# SCH_-_Peripheral.net
KiCad netlist of a schematic drawn in Altium Designer
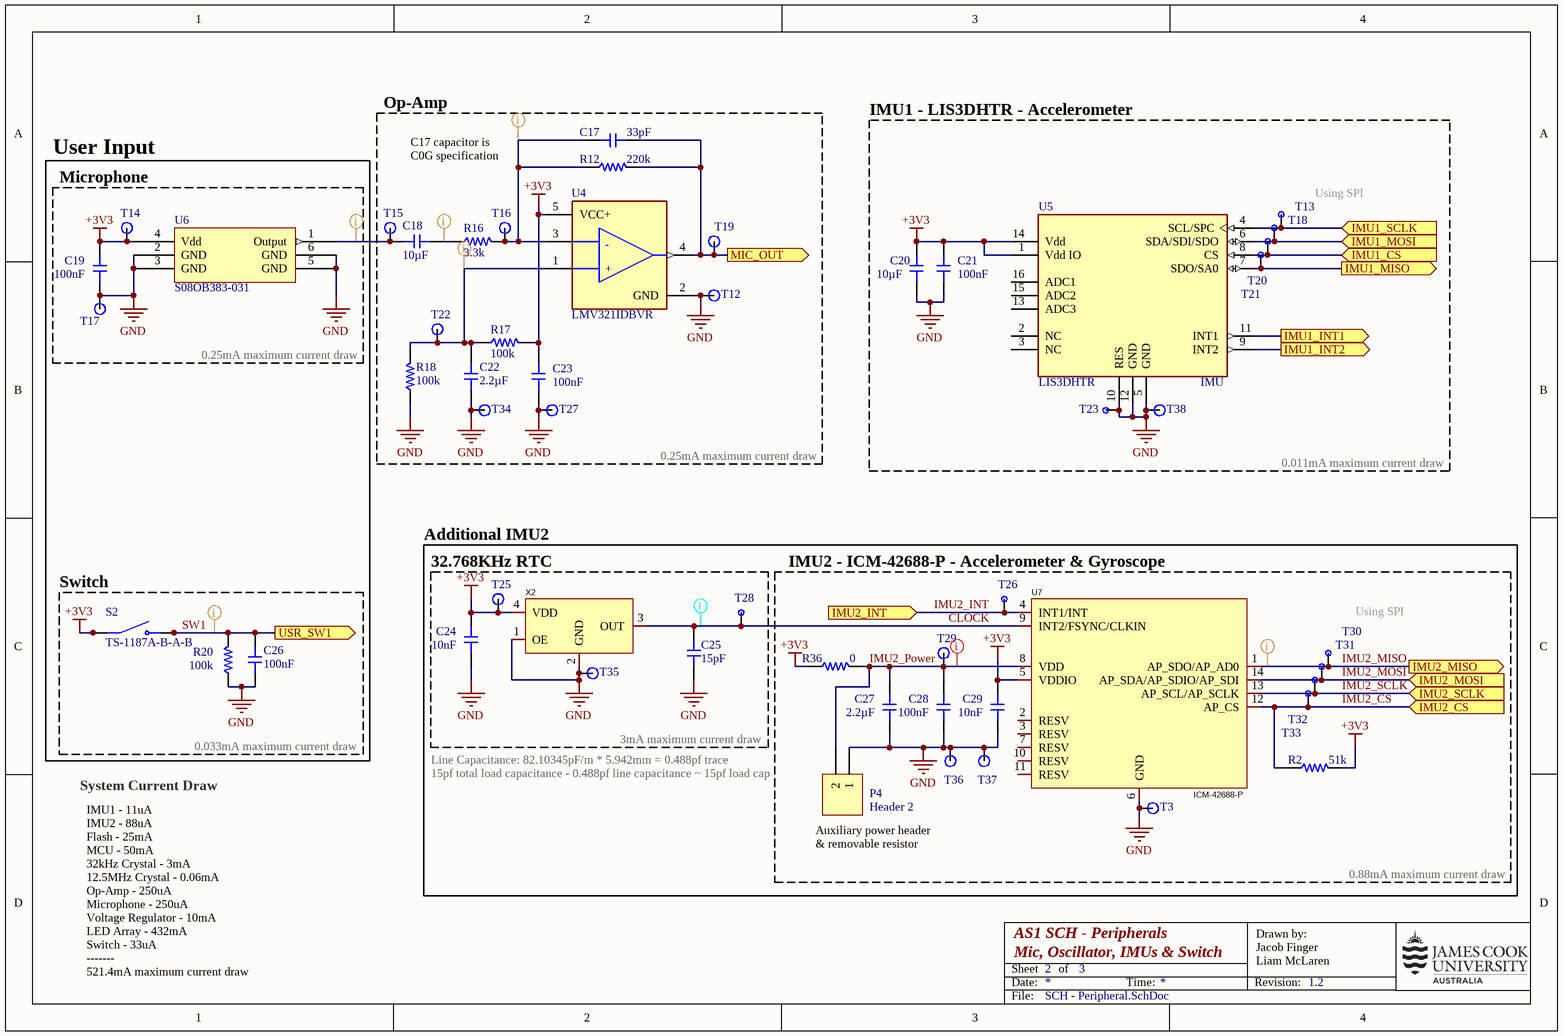
[diagram p0: SCH - Peripheral.SchDoc]

(export (version "E")
  (design (tool "Eeschema 10.0.6"))
  (components
    (comp (ref "C17")
      (value "33pF")
      (footprint "CAP-0402")
      (description "Capacitor, Ceramic (MLCC), 33pF, ±5%, 50V, C0G, ±5%, SMD 0402")
      (fields (field (name "TOLERANCE") "5%") (field (name "MANUFACTURER PART NUMBER") "0402CG330J500NT"))
      (libsource (lib "Finmac Systems") (part "GRM21BR61H106KE43L"))
    )
    (comp (ref "C18")
      (value "10µF")
      (footprint "CAP-0402")
      (description "Capacitor, Ceramic (MLCC), 10uF, ±20%, 6.3V, X5R, ±20%, SMD 0402")
      (fields
        (field (name "MANUFACTURER") "Samsung Electro-Mechanics")
        (field (name "JLCPCB PART NUMBER") "C15525")
      )
      (libsource (lib "Finmac Systems") (part "GRM21BR61H106KE43L"))
    )
    (comp (ref "C19")
      (value "100nF")
      (footprint "CAP-0402")
      (description "Capacitor, Ceramic (MLCC), 100nF, ±10%, 50V, X7R, ±10%, SMD 0402")
      (fields
        (field (name "MANUFACTURER PART NUMBER") "CL05B104KB54PNC")
        (field (name "MANUFACTURER") "Samsung Electro-Mechanics")
      )
      (libsource (lib "Finmac Systems") (part "GRM21BR61H106KE43L"))
    )
    (comp (ref "C20")
      (value "10µF")
      (footprint "CAP-0402")
      (description "Capacitor, Ceramic (MLCC), 10uF, ±20%, 6.3V, X5R, ±20%, SMD 0402")
      (fields
        (field (name "MANUFACTURER") "Samsung Electro-Mechanics")
        (field (name "JLCPCB PART NUMBER") "C15525")
      )
      (libsource (lib "Finmac Systems") (part "GRM21BR61H106KE43L"))
    )
    (comp (ref "C21")
      (value "100nF")
      (footprint "CAP-0402")
      (description "Capacitor, Ceramic (MLCC), 100nF, ±10%, 50V, X7R, ±10%, SMD 0402")
      (fields
        (field (name "MANUFACTURER PART NUMBER") "CL05B104KB54PNC")
        (field (name "MANUFACTURER") "Samsung Electro-Mechanics")
      )
      (libsource (lib "Finmac Systems") (part "GRM21BR61H106KE43L"))
    )
    (comp (ref "C22")
      (value "2.2µF")
      (footprint "CAP-0402")
      (description "Capacitor, Ceramic (MLCC), 2.2uF, ±20%, 6.3V, X5R, ±20%, SMD 0402")
      (fields
        (field (name "MANUFACTURER PART NUMBER") "CL05A225MQ5NSNC")
        (field (name "MANUFACTURER") "Samsung Electro-Mechanics")
      )
      (libsource (lib "Finmac Systems") (part "GRM21BR61H106KE43L"))
    )
    (comp (ref "C23")
      (value "100nF")
      (footprint "CAP-0402")
      (description "Capacitor, Ceramic (MLCC), 100nF, ±10%, 50V, X7R, ±10%, SMD 0402")
      (fields
        (field (name "MANUFACTURER PART NUMBER") "CL05B104KB54PNC")
        (field (name "MANUFACTURER") "Samsung Electro-Mechanics")
      )
      (libsource (lib "Finmac Systems") (part "GRM21BR61H106KE43L"))
    )
    (comp (ref "C24")
      (value "10nF")
      (footprint "CAP-0402")
      (description "Capacitor, Ceramic (MLCC), 10nF, ±10%, 50V, X7R, ±10%, SMD 0402")
      (fields (field (name "JLCPCB BASIC PART") "Yes") (field (name "JLCPCB PART NUMBER") "C15195"))
      (libsource (lib "Finmac Systems") (part "GRM21BR61H106KE43L"))
    )
    (comp (ref "C25")
      (value "15pF")
      (footprint "CAP-0402")
      (description "Capacitor, Ceramic (MLCC), 15pF, ±5%, 50V, C0G, ±5%, SMD 0402")
      (fields (field (name "TOLERANCE") "5%") (field (name "MANUFACTURER PART NUMBER") "0402CG150J500NT"))
      (libsource (lib "Finmac Systems") (part "GRM21BR61H106KE43L"))
    )
    (comp (ref "C26")
      (value "100nF")
      (footprint "CAP-0402")
      (description "Capacitor, Ceramic (MLCC), 100nF, ±10%, 16V, X7R, ±10%, SMD 0402")
      (fields
        (field (name "MANUFACTURER PART NUMBER") "CL05B104KO5NNNC")
        (field (name "MANUFACTURER") "Samsung Electro-Mechanics")
      )
      (libsource (lib "Finmac Systems") (part "GRM21BR61H106KE43L"))
    )
    (comp (ref "C27")
      (value "2.2µF")
      (footprint "CAP-0402")
      (description "Capacitor, Ceramic (MLCC), 2.2uF, ±20%, 6.3V, X5R, ±20%, SMD 0402")
      (fields
        (field (name "MANUFACTURER PART NUMBER") "CL05A225MQ5NSNC")
        (field (name "MANUFACTURER") "Samsung Electro-Mechanics")
      )
      (libsource (lib "Finmac Systems") (part "GRM21BR61H106KE43L"))
    )
    (comp (ref "C28")
      (value "100nF")
      (footprint "CAP-0402")
      (description "Capacitor, Ceramic (MLCC), 100nF, ±10%, 50V, X7R, ±10%, SMD 0402")
      (fields
        (field (name "MANUFACTURER PART NUMBER") "CL05B104KB54PNC")
        (field (name "MANUFACTURER") "Samsung Electro-Mechanics")
      )
      (libsource (lib "Finmac Systems") (part "GRM21BR61H106KE43L"))
    )
    (comp (ref "C29")
      (value "10nF")
      (footprint "CAP-0402")
      (description "Capacitor, Ceramic (MLCC), 10nF, ±10%, 50V, X7R, ±10%, SMD 0402")
      (fields (field (name "JLCPCB BASIC PART") "Yes") (field (name "JLCPCB PART NUMBER") "C15195"))
      (libsource (lib "Finmac Systems") (part "GRM21BR61H106KE43L"))
    )
    (comp (ref "P4")
      (value "Header 2")
      (footprint "HDR1X2")
      (description "Header, 2-Pin")
      (fields (field (name "PUBLISHER") "Altium Limited"))
      (libsource (lib "James Cook University") (part "Header 2H"))
    )
    (comp (ref "R2")
      (value "51k")
      (footprint "RES-0402")
      (description "Resistor, 51kΩ, ±1%, 62.5mW, 50V, ±100ppm/℃, -55℃~+155℃, SMD 0402")
      (fields
        (field (name "MANUFACTURER") "Uniroyal")
        (field (name "MANUFACTURER PART NUMBER") "0402WGF5102TCE")
      )
      (libsource (lib "Finmac Systems") (part "1206W4F7500T5E"))
    )
    (comp (ref "R12")
      (value "220k")
      (footprint "RES-0603")
      (description "Resistor, 220kΩ, ±1%, 100mW, 75V, ±100ppm/℃, -55℃~+155℃, SMD 0603")
      (fields (field (name "TOLERANCE") "1%") (field (name "MANUFACTURER PART NUMBER") "0603WAF2203T5E"))
      (libsource (lib "Finmac Systems") (part "1206W4F7500T5E"))
    )
    (comp (ref "R16")
      (value "3.3k")
      (footprint "RES-0402")
      (description "Resistor, 3.3kΩ, ±1%, 62.5mW, 50V, ±100ppm/℃, -55℃~+155℃, SMD 0402")
      (fields (field (name "JLCPCB PART NUMBER") "C25890") (field (name "MANUFACTURER") "Uniroyal"))
      (libsource (lib "Finmac Systems") (part "1206W4F7500T5E"))
    )
    (comp (ref "R17")
      (value "100k")
      (footprint "RES-0402")
      (description "Resistor, 100kΩ, ±1%, 62.5mW, 50V, ±100ppm/℃, -55℃~+155℃, SMD 0402")
      (fields (field (name "TOLERANCE") "1%") (field (name "MANUFACTURER") "Uniroyal"))
      (libsource (lib "Finmac Systems") (part "1206W4F7500T5E"))
    )
    (comp (ref "R18")
      (value "100k")
      (footprint "RES-0402")
      (description "Resistor, 100kΩ, ±1%, 62.5mW, 50V, ±100ppm/℃, -55℃~+155℃, SMD 0402")
      (fields (field (name "TOLERANCE") "1%") (field (name "MANUFACTURER") "Uniroyal"))
      (libsource (lib "Finmac Systems") (part "1206W4F7500T5E"))
    )
    (comp (ref "R20")
      (value "100k")
      (footprint "RES-0402")
      (description "Resistor, 100kΩ, ±1%, 62.5mW, 50V, ±100ppm/℃, -55℃~+155℃, SMD 0402")
      (fields (field (name "TOLERANCE") "1%") (field (name "MANUFACTURER") "Uniroyal"))
      (libsource (lib "Finmac Systems") (part "1206W4F7500T5E"))
    )
    (comp (ref "R36")
      (value "0")
      (footprint "RES-0402")
      (description "Resistor, 0Ω, ±1%, 62.5mW, 50V, ±800ppm/℃, -55℃~+155℃, SMD 0402")
      (fields (field (name "JLCPCB PART NUMBER") "C17168") (field (name "TOLERANCE") "1%"))
      (libsource (lib "Finmac Systems") (part "1206W4F7500T5E"))
    )
    (comp (ref "S2")
      (value "TS-1187A-B-A-B")
      (footprint "SW_TS-1187A-B-A-B")
      (description "SPST 50mA @ 12VDC Top Actuated Round Button 160gf SMD Tactile Switches RoHS")
      (fields (field (name "JLCPCB PART") "C318884"))
      (libsource (lib "Finmac Systems") (part "CMP-051-000000-5"))
    )
    (comp (ref "T3")
      (value "TP")
      (footprint "TestPoint")
      (libsource (lib "DatumPenLibrary") (part "TestPoint"))
    )
    (comp (ref "T12")
      (value "TP")
      (footprint "TestPoint")
      (libsource (lib "DatumPenLibrary") (part "TestPoint"))
    )
    (comp (ref "T13")
      (value "TP")
      (footprint "TestPoint - Small")
      (libsource (lib "DatumPenLibrary") (part "TestPoint Small"))
    )
    (comp (ref "T14")
      (value "TP")
      (footprint "TestPoint")
      (libsource (lib "DatumPenLibrary") (part "TestPoint"))
    )
    (comp (ref "T15")
      (value "TP")
      (footprint "TestPoint")
      (libsource (lib "DatumPenLibrary") (part "TestPoint"))
    )
    (comp (ref "T16")
      (value "TP")
      (footprint "TestPoint")
      (libsource (lib "DatumPenLibrary") (part "TestPoint"))
    )
    (comp (ref "T17")
      (value "TP")
      (footprint "TestPoint")
      (libsource (lib "DatumPenLibrary") (part "TestPoint"))
    )
    (comp (ref "T18")
      (value "TP")
      (footprint "TestPoint - Small")
      (libsource (lib "DatumPenLibrary") (part "TestPoint Small"))
    )
    (comp (ref "T19")
      (value "TP")
      (footprint "TestPoint")
      (libsource (lib "DatumPenLibrary") (part "TestPoint"))
    )
    (comp (ref "T20")
      (value "TP")
      (footprint "TestPoint - Small")
      (libsource (lib "DatumPenLibrary") (part "TestPoint Small"))
    )
    (comp (ref "T21")
      (value "TP")
      (footprint "TestPoint - Small")
      (libsource (lib "DatumPenLibrary") (part "TestPoint Small"))
    )
    (comp (ref "T22")
      (value "TP")
      (footprint "TestPoint")
      (libsource (lib "DatumPenLibrary") (part "TestPoint"))
    )
    (comp (ref "T23")
      (value "TP")
      (footprint "TestPoint - Small")
      (libsource (lib "DatumPenLibrary") (part "TestPoint Small"))
    )
    (comp (ref "T25")
      (value "TP")
      (footprint "TestPoint")
      (libsource (lib "DatumPenLibrary") (part "TestPoint"))
    )
    (comp (ref "T26")
      (value "TP")
      (footprint "TestPoint - Small")
      (libsource (lib "DatumPenLibrary") (part "TestPoint Small"))
    )
    (comp (ref "T27")
      (value "TP")
      (footprint "TestPoint")
      (libsource (lib "DatumPenLibrary") (part "TestPoint"))
    )
    (comp (ref "T28")
      (value "TP")
      (footprint "TestPoint - Small")
      (libsource (lib "DatumPenLibrary") (part "TestPoint Small"))
    )
    (comp (ref "T29")
      (value "TP")
      (footprint "TestPoint")
      (libsource (lib "DatumPenLibrary") (part "TestPoint"))
    )
    (comp (ref "T30")
      (value "TP")
      (footprint "TestPoint - Small")
      (libsource (lib "DatumPenLibrary") (part "TestPoint Small"))
    )
    (comp (ref "T31")
      (value "TP")
      (footprint "TestPoint - Small")
      (libsource (lib "DatumPenLibrary") (part "TestPoint Small"))
    )
    (comp (ref "T32")
      (value "TP")
      (footprint "TestPoint - Small")
      (libsource (lib "DatumPenLibrary") (part "TestPoint Small"))
    )
    (comp (ref "T33")
      (value "TP")
      (footprint "TestPoint - Small")
      (libsource (lib "DatumPenLibrary") (part "TestPoint Small"))
    )
    (comp (ref "T34")
      (value "TP")
      (footprint "TestPoint")
      (libsource (lib "DatumPenLibrary") (part "TestPoint"))
    )
    (comp (ref "T35")
      (value "TP")
      (footprint "TestPoint")
      (libsource (lib "DatumPenLibrary") (part "TestPoint"))
    )
    (comp (ref "T36")
      (value "TP")
      (footprint "TestPoint")
      (libsource (lib "DatumPenLibrary") (part "TestPoint"))
    )
    (comp (ref "T37")
      (value "TP")
      (footprint "TestPoint")
      (libsource (lib "DatumPenLibrary") (part "TestPoint"))
    )
    (comp (ref "T38")
      (value "TP")
      (footprint "TestPoint")
      (libsource (lib "DatumPenLibrary") (part "TestPoint"))
    )
    (comp (ref "U4")
      (value "LMV321IDBVR")
      (footprint "FP-DBV0005A-MFG")
      (description "General Purpose Amplifier 1 Circuit Rail-to-Rail SOT-23-5")
      (fields (field (name "JLCPCB PART") "C7972"))
      (libsource (lib "SCH_LIB_Assignment1") (part "CMP-00012-2"))
    )
    (comp (ref "U5")
      (value "LIS3DHTR")
      (footprint "FP-LGA-16-7983231-MFG")
      (description "ACCEL 2-16G I2C/SPI 16LGA")
      (fields (field (name "JLCPCB PART") "C15134"))
      (libsource (lib "SCH_LIB_Assignment1") (part "CMP-00010-2"))
    )
    (comp (ref "U6")
      (value "S08OB383-031")
      (footprint "Goertek_S08OB381-026")
      (description "MEMS Microphone SMD 3.76x3x1.1mm")
      (fields (field (name "JLCPCB PART") "C233789"))
      (libsource (lib "SCH_LIB_Assignment1") (part "CMP-00027-00000-1"))
    )
    (comp (ref "U7")
      (value "IMU IC")
      (footprint "LGA-14_L3.0-W2.5-P0.50-TL")
      (description "ICM-42688-P LGA-14(2.5x3) Attitude Sensor/Gyroscope")
      (fields
        (field (name "MANUFACTURER") "TDK InvenSense(应美盛)")
        (field (name "MANUFACTURER PART") "ICM-42688-P")
        (field (name "LCSC PART #") "C1850418")
      )
      (libsource (lib "DatumPenLibrary") (part "ICM-42688-P"))
    )
    (comp (ref "X2")
      (value "HSO221S RTC")
      (footprint "OSC-SMD_4P-L2.5-W2.0-BL")
      (description "HSO221S RTC - 3.3V 3mA ±30ppm 32.768kHz SMD2520-4P Oscillators ROHS")
      (fields
        (field (name "MANUFACTURER") "HELE(台湾加高)")
        (field (name "MANUFACTURER PART") "S2H32768KF3CHC-IT")
      )
      (libsource (lib "DatumPenLibrary") (part "S2H32768KF3CHC-IT"))
    )
  )
  (nets
    (net (code "1") (name "+3V3") (class "Default")
      (node (ref "C19") (pin "2") (pinfunction "2_2") (pintype "passive"))
      (node (ref "C20") (pin "1") (pinfunction "1_1") (pintype "passive"))
      (node (ref "C21") (pin "2") (pinfunction "2_2") (pintype "passive"))
      (node (ref "C23") (pin "2") (pinfunction "2_2") (pintype "passive"))
      (node (ref "C24") (pin "2") (pinfunction "2_2") (pintype "passive"))
      (node (ref "C29") (pin "2") (pinfunction "2_2") (pintype "passive"))
      (node (ref "R17") (pin "2") (pinfunction "2_2") (pintype "passive"))
      (node (ref "R2") (pin "2") (pinfunction "2_2") (pintype "passive"))
      (node (ref "R36") (pin "1") (pinfunction "1_1") (pintype "passive"))
      (node (ref "S2") (pin "A") (pinfunction "COM_A") (pintype "passive"))
      (node (ref "S2") (pin "B") (pinfunction "COM_B") (pintype "passive"))
      (node (ref "T14") (pin "1") (pinfunction "TP_1") (pintype "passive"))
      (node (ref "T25") (pin "1") (pinfunction "TP_1") (pintype "passive"))
      (node (ref "U4") (pin "5") (pinfunction "VCC+_5") (pintype "power_in"))
      (node (ref "U5") (pin "1") (pinfunction "Vdd_IO_1") (pintype "power_in"))
      (node (ref "U5") (pin "14") (pinfunction "Vdd_14") (pintype "power_in"))
      (node (ref "U6") (pin "4") (pinfunction "Vdd_4") (pintype "power_in"))
      (node (ref "U7") (pin "5") (pinfunction "VDDIO_5") (pintype "passive"))
      (node (ref "X2") (pin "4") (pinfunction "VDD_4") (pintype "passive"))
    )
    (net (code "2") (name "/CLOCK") (class "Default")
      (node (ref "C25") (pin "2") (pinfunction "2_2") (pintype "passive"))
      (node (ref "T28") (pin "1") (pinfunction "TP_1") (pintype "passive"))
      (node (ref "U7") (pin "9") (pinfunction "INT2/FSYNC/CLKIN_9") (pintype "passive"))
      (node (ref "X2") (pin "3") (pinfunction "OUT_3") (pintype "passive"))
    )
    (net (code "3") (name "/IMU1_CS") (class "Default")
      (node (ref "T20") (pin "1") (pinfunction "TP_1") (pintype "passive"))
      (node (ref "U5") (pin "8") (pinfunction "CS_8") (pintype "input"))
    )
    (net (code "4") (name "/IMU1_INT1") (class "Default")
      (node (ref "U5") (pin "11") (pinfunction "INT1_11") (pintype "output"))
    )
    (net (code "5") (name "/IMU1_INT2") (class "Default")
      (node (ref "U5") (pin "9") (pinfunction "INT2_9") (pintype "output"))
    )
    (net (code "6") (name "/IMU1_MISO") (class "Default")
      (node (ref "T21") (pin "1") (pinfunction "TP_1") (pintype "passive"))
      (node (ref "U5") (pin "7") (pinfunction "SDO/SA0_7") (pintype "bidirectional"))
    )
    (net (code "7") (name "/IMU1_MOSI") (class "Default")
      (node (ref "T18") (pin "1") (pinfunction "TP_1") (pintype "passive"))
      (node (ref "U5") (pin "6") (pinfunction "SDA/SDI/SDO_6") (pintype "bidirectional"))
    )
    (net (code "8") (name "/IMU1_SCLK") (class "Default")
      (node (ref "T13") (pin "1") (pinfunction "TP_1") (pintype "passive"))
      (node (ref "U5") (pin "4") (pinfunction "SCL/SPC_4") (pintype "input"))
    )
    (net (code "9") (name "/IMU2_CS") (class "Default")
      (node (ref "R2") (pin "1") (pinfunction "1_1") (pintype "passive"))
      (node (ref "T33") (pin "1") (pinfunction "TP_1") (pintype "passive"))
      (node (ref "U7") (pin "12") (pinfunction "AP_CS_12") (pintype "passive"))
    )
    (net (code "10") (name "/IMU2_INT") (class "Default")
      (node (ref "T26") (pin "1") (pinfunction "TP_1") (pintype "passive"))
      (node (ref "U7") (pin "4") (pinfunction "INT1/INT_4") (pintype "passive"))
    )
    (net (code "11") (name "/IMU2_MISO") (class "Default")
      (node (ref "T30") (pin "1") (pinfunction "TP_1") (pintype "passive"))
      (node (ref "U7") (pin "1") (pinfunction "AP_SDO/AP_AD0_1") (pintype "passive"))
    )
    (net (code "12") (name "/IMU2_MOSI") (class "Default")
      (node (ref "T31") (pin "1") (pinfunction "TP_1") (pintype "passive"))
      (node (ref "U7") (pin "14") (pinfunction "AP_SDA/AP_SDIO/AP_SDI_14") (pintype "passive"))
    )
    (net (code "13") (name "/IMU2_Power") (class "Default")
      (node (ref "C27") (pin "2") (pinfunction "2_2") (pintype "passive"))
      (node (ref "C28") (pin "2") (pinfunction "2_2") (pintype "passive"))
      (node (ref "P4") (pin "2") (pinfunction "2_2") (pintype "passive"))
      (node (ref "R36") (pin "2") (pinfunction "2_2") (pintype "passive"))
      (node (ref "T29") (pin "1") (pinfunction "TP_1") (pintype "passive"))
      (node (ref "U7") (pin "8") (pinfunction "VDD_8") (pintype "passive"))
    )
    (net (code "14") (name "/IMU2_SCLK") (class "Default")
      (node (ref "T32") (pin "1") (pinfunction "TP_1") (pintype "passive"))
      (node (ref "U7") (pin "13") (pinfunction "AP_SCL/AP_SCLK_13") (pintype "passive"))
    )
    (net (code "15") (name "/MIC_OUT") (class "Default")
      (node (ref "C17") (pin "2") (pinfunction "2_2") (pintype "passive"))
      (node (ref "R12") (pin "2") (pinfunction "2_2") (pintype "passive"))
      (node (ref "T19") (pin "1") (pinfunction "TP_1") (pintype "passive"))
      (node (ref "U4") (pin "4") (pinfunction "OUT_4") (pintype "output"))
    )
    (net (code "16") (name "/SW1") (class "Default")
      (node (ref "C26") (pin "2") (pinfunction "2_2") (pintype "passive"))
      (node (ref "R20") (pin "2") (pinfunction "2_2") (pintype "passive"))
      (node (ref "S2") (pin "C") (pinfunction "NO_C") (pintype "passive"))
      (node (ref "S2") (pin "D") (pinfunction "NO_D") (pintype "passive"))
    )
    (net (code "17") (name "GND") (class "Default")
      (node (ref "C19") (pin "1") (pinfunction "1_1") (pintype "passive"))
      (node (ref "C20") (pin "2") (pinfunction "2_2") (pintype "passive"))
      (node (ref "C21") (pin "1") (pinfunction "1_1") (pintype "passive"))
      (node (ref "C22") (pin "1") (pinfunction "1_1") (pintype "passive"))
      (node (ref "C23") (pin "1") (pinfunction "1_1") (pintype "passive"))
      (node (ref "C24") (pin "1") (pinfunction "1_1") (pintype "passive"))
      (node (ref "C25") (pin "1") (pinfunction "1_1") (pintype "passive"))
      (node (ref "C26") (pin "1") (pinfunction "1_1") (pintype "passive"))
      (node (ref "C27") (pin "1") (pinfunction "1_1") (pintype "passive"))
      (node (ref "C28") (pin "1") (pinfunction "1_1") (pintype "passive"))
      (node (ref "C29") (pin "1") (pinfunction "1_1") (pintype "passive"))
      (node (ref "P4") (pin "1") (pinfunction "1_1") (pintype "passive"))
      (node (ref "R18") (pin "1") (pinfunction "1_1") (pintype "passive"))
      (node (ref "R20") (pin "1") (pinfunction "1_1") (pintype "passive"))
      (node (ref "T12") (pin "1") (pinfunction "TP_1") (pintype "passive"))
      (node (ref "T17") (pin "1") (pinfunction "TP_1") (pintype "passive"))
      (node (ref "T23") (pin "1") (pinfunction "TP_1") (pintype "passive"))
      (node (ref "T27") (pin "1") (pinfunction "TP_1") (pintype "passive"))
      (node (ref "T3") (pin "1") (pinfunction "TP_1") (pintype "passive"))
      (node (ref "T34") (pin "1") (pinfunction "TP_1") (pintype "passive"))
      (node (ref "T35") (pin "1") (pinfunction "TP_1") (pintype "passive"))
      (node (ref "T36") (pin "1") (pinfunction "TP_1") (pintype "passive"))
      (node (ref "T37") (pin "1") (pinfunction "TP_1") (pintype "passive"))
      (node (ref "T38") (pin "1") (pinfunction "TP_1") (pintype "passive"))
      (node (ref "U4") (pin "2") (pinfunction "GND_2") (pintype "power_in"))
      (node (ref "U5") (pin "10") (pinfunction "RES_10") (pintype "passive"))
      (node (ref "U5") (pin "12") (pinfunction "GND_12") (pintype "power_in"))
      (node (ref "U5") (pin "5") (pinfunction "GND_5") (pintype "power_in"))
      (node (ref "U6") (pin "2") (pinfunction "GND_2") (pintype "power_in"))
      (node (ref "U6") (pin "3") (pinfunction "GND_3") (pintype "power_in"))
      (node (ref "U6") (pin "5") (pinfunction "GND_5") (pintype "power_in"))
      (node (ref "U6") (pin "6") (pinfunction "GND_6") (pintype "power_in"))
      (node (ref "U7") (pin "6") (pinfunction "GND_6") (pintype "passive"))
      (node (ref "X2") (pin "1") (pinfunction "OE_1") (pintype "passive"))
      (node (ref "X2") (pin "2") (pinfunction "GND_2") (pintype "passive"))
    )
    (net (code "18") (name "Net-(C18-Pad2)") (class "Default")
      (node (ref "C18") (pin "2") (pinfunction "2_2") (pintype "passive"))
      (node (ref "R16") (pin "1") (pinfunction "1_1") (pintype "passive"))
    )
    (net (code "19") (name "Net-(T15-TP)") (class "Default")
      (node (ref "C18") (pin "1") (pinfunction "1_1") (pintype "passive"))
      (node (ref "T15") (pin "1") (pinfunction "TP_1") (pintype "passive"))
      (node (ref "U6") (pin "1") (pinfunction "Output_1") (pintype "output"))
    )
    (net (code "20") (name "Net-(T16-TP)") (class "Default")
      (node (ref "C17") (pin "1") (pinfunction "1_1") (pintype "passive"))
      (node (ref "R12") (pin "1") (pinfunction "1_1") (pintype "passive"))
      (node (ref "R16") (pin "2") (pinfunction "2_2") (pintype "passive"))
      (node (ref "T16") (pin "1") (pinfunction "TP_1") (pintype "passive"))
      (node (ref "U4") (pin "3") (pinfunction "1IN-_3") (pintype "tri_state"))
    )
    (net (code "21") (name "Net-(T22-TP)") (class "Default")
      (node (ref "C22") (pin "2") (pinfunction "2_2") (pintype "passive"))
      (node (ref "R17") (pin "1") (pinfunction "1_1") (pintype "passive"))
      (node (ref "R18") (pin "2") (pinfunction "2_2") (pintype "passive"))
      (node (ref "T22") (pin "1") (pinfunction "TP_1") (pintype "passive"))
      (node (ref "U4") (pin "1") (pinfunction "1IN+_1") (pintype "tri_state"))
    )
    (net (code "22") (name "unconnected-(U5-ADC1-Pad16)") (class "Default")
      (node (ref "U5") (pin "16") (pinfunction "ADC1_16") (pintype "passive"))
    )
    (net (code "23") (name "unconnected-(U5-ADC2-Pad15)") (class "Default")
      (node (ref "U5") (pin "15") (pinfunction "ADC2_15") (pintype "passive"))
    )
    (net (code "24") (name "unconnected-(U5-ADC3-Pad13)") (class "Default")
      (node (ref "U5") (pin "13") (pinfunction "ADC3_13") (pintype "passive"))
    )
    (net (code "25") (name "unconnected-(U5-NC-Pad2)") (class "Default")
      (node (ref "U5") (pin "2") (pinfunction "NC_2") (pintype "passive"))
    )
    (net (code "26") (name "unconnected-(U5-NC-Pad3)") (class "Default")
      (node (ref "U5") (pin "3") (pinfunction "NC_3") (pintype "passive"))
    )
    (net (code "27") (name "unconnected-(U7-RESV-Pad2)") (class "Default")
      (node (ref "U7") (pin "2") (pinfunction "RESV_2") (pintype "passive"))
    )
    (net (code "28") (name "unconnected-(U7-RESV-Pad3)") (class "Default")
      (node (ref "U7") (pin "3") (pinfunction "RESV_3") (pintype "passive"))
    )
    (net (code "29") (name "unconnected-(U7-RESV-Pad7)") (class "Default")
      (node (ref "U7") (pin "7") (pinfunction "RESV_7") (pintype "passive"))
    )
    (net (code "30") (name "unconnected-(U7-RESV-Pad10)") (class "Default")
      (node (ref "U7") (pin "10") (pinfunction "RESV_10") (pintype "passive"))
    )
    (net (code "31") (name "unconnected-(U7-RESV-Pad11)") (class "Default")
      (node (ref "U7") (pin "11") (pinfunction "RESV_11") (pintype "passive"))
    )
  )
)
